# oLoRa-part-thi.net
KiCad netlist of a schematic drawn in EasyEDA
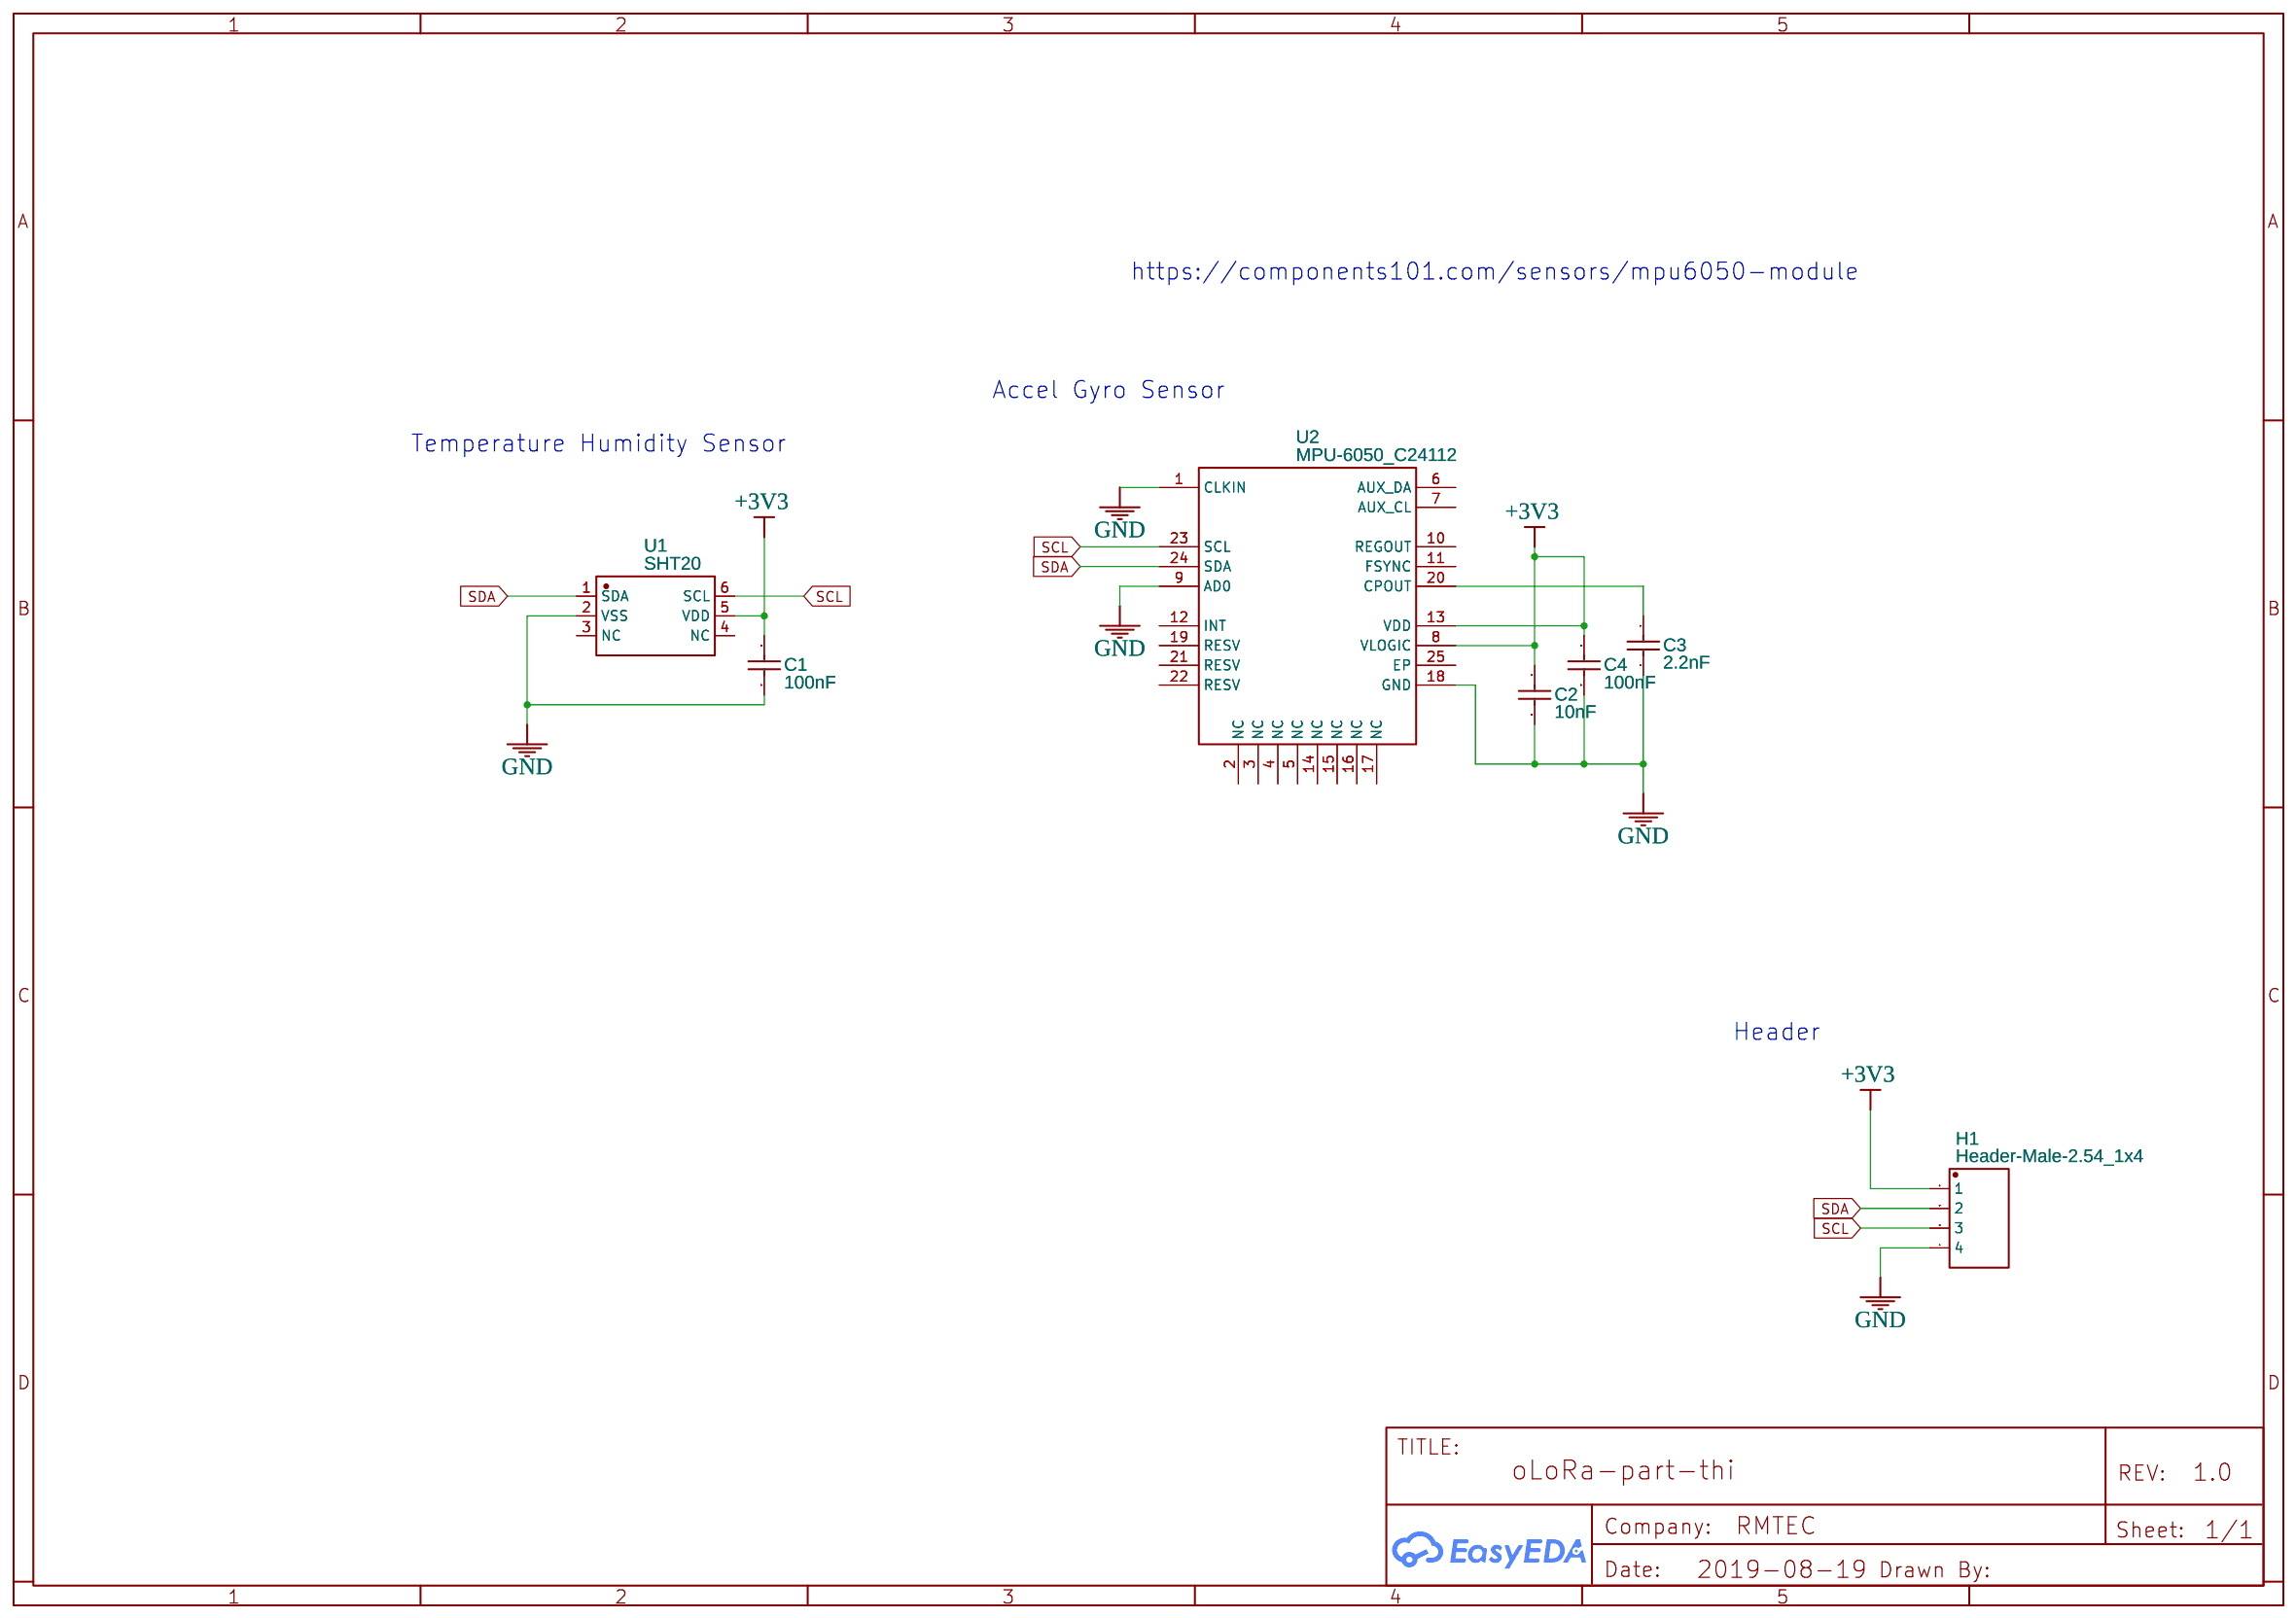
[diagram p0: schematic sheet]

(export (version "E")
  (design (tool "Eeschema 10.0.6"))
  (components
    (comp (ref "C1")
      (value "100nF")
      (fields
        (field (name "BOM_Manufacturer Part") "0603B104K500NT")
        (field (name "BOM_Supplier Part") "C30926")
      )
      (libsource (lib "") (part "0603B104K500NT"))
    )
    (comp (ref "C2")
      (value "10nF")
      (fields
        (field (name "BOM_Manufacturer Part") "CC0603KRX7R9BB103")
        (field (name "BOM_Supplier Part") "C100042")
      )
      (libsource (lib "") (part "CC0603KRX7R9BB103"))
    )
    (comp (ref "C3")
      (value "2.2nF")
      (fields
        (field (name "BOM_Manufacturer Part") "CC0603KRX7R9BB222")
        (field (name "BOM_Supplier Part") "C107082")
      )
      (libsource (lib "") (part "CC0603KRX7R9BB222"))
    )
    (comp (ref "C4")
      (value "100nF")
      (fields
        (field (name "BOM_Manufacturer Part") "0603B104K500NT")
        (field (name "BOM_Supplier Part") "C30926")
      )
      (libsource (lib "") (part "0603B104K500NT"))
    )
    (comp (ref "H1")
      (value "Header-Male-2.54_1x4")
      (fields
        (field (name "BOM_Manufacturer Part") "210S-1*4P L=11.6MMGold-plated black")
        (field (name "BOM_Supplier Part") "C124378")
      )
      (libsource (lib "") (part "Unknown_990_610"))
    )
    (comp (ref "U1")
      (value "SHT20")
      (fields (field (name "BOM_Supplier Part") "C53865"))
      (libsource (lib "") (part "Unknown_325_305"))
    )
    (comp (ref "U2")
      (value "MPU-6050_C24112")
      (fields (field (name "BOM_Manufacturer Part") "MPU-6050") (field (name "BOM_Supplier Part") "C24112"))
      (libsource (lib "") (part "Unknown_660_310"))
    )
  )
  (nets
    (net (code "1") (name "+3V3") (class "Default")
      (node (ref "C1") (pin "1") (pinfunction "1_1") (pintype "input"))
      (node (ref "C2") (pin "2") (pinfunction "2_2") (pintype "input"))
      (node (ref "C4") (pin "1") (pinfunction "1_1") (pintype "input"))
      (node (ref "H1") (pin "1") (pinfunction "1_1") (pintype "unspecified"))
      (node (ref "U1") (pin "5") (pinfunction "VDD_5") (pintype "unspecified"))
      (node (ref "U2") (pin "13") (pinfunction "VDD_13") (pintype "passive"))
      (node (ref "U2") (pin "8") (pinfunction "VLOGIC_8") (pintype "passive"))
    )
    (net (code "2") (name "GND") (class "Default")
      (node (ref "C1") (pin "2") (pinfunction "2_2") (pintype "input"))
      (node (ref "C2") (pin "1") (pinfunction "1_1") (pintype "input"))
      (node (ref "C3") (pin "1") (pinfunction "1_1") (pintype "input"))
      (node (ref "C4") (pin "2") (pinfunction "2_2") (pintype "input"))
      (node (ref "H1") (pin "4") (pinfunction "4_4") (pintype "unspecified"))
      (node (ref "U1") (pin "2") (pinfunction "VSS_2") (pintype "unspecified"))
      (node (ref "U2") (pin "1") (pinfunction "CLKIN_1") (pintype "input"))
      (node (ref "U2") (pin "18") (pinfunction "GND_18") (pintype "passive"))
      (node (ref "U2") (pin "9") (pinfunction "AD0_9") (pintype "input"))
    )
    (net (code "3") (name "Net-(U2-CPOUT)") (class "Default")
      (node (ref "C3") (pin "2") (pinfunction "2_2") (pintype "input"))
      (node (ref "U2") (pin "20") (pinfunction "CPOUT_20") (pintype "output"))
    )
    (net (code "4") (name "SCL") (class "Default")
      (node (ref "H1") (pin "3") (pinfunction "3_3") (pintype "unspecified"))
      (node (ref "U1") (pin "6") (pinfunction "SCL_6") (pintype "unspecified"))
      (node (ref "U2") (pin "23") (pinfunction "SCL_23") (pintype "input"))
    )
    (net (code "5") (name "SDA") (class "Default")
      (node (ref "H1") (pin "2") (pinfunction "2_2") (pintype "unspecified"))
      (node (ref "U1") (pin "1") (pinfunction "SDA_1") (pintype "unspecified"))
      (node (ref "U2") (pin "24") (pinfunction "SDA_24") (pintype "unspecified"))
    )
    (net (code "6") (name "unconnected-(U1-NC-Pad3)") (class "Default")
      (node (ref "U1") (pin "3") (pinfunction "NC_3") (pintype "unspecified"))
    )
    (net (code "7") (name "unconnected-(U1-NC-Pad4)") (class "Default")
      (node (ref "U1") (pin "4") (pinfunction "NC_4") (pintype "unspecified"))
    )
    (net (code "8") (name "unconnected-(U2-AUX_CL-Pad7)") (class "Default")
      (node (ref "U2") (pin "7") (pinfunction "AUX_CL_7") (pintype "unspecified"))
    )
    (net (code "9") (name "unconnected-(U2-AUX_DA-Pad6)") (class "Default")
      (node (ref "U2") (pin "6") (pinfunction "AUX_DA_6") (pintype "unspecified"))
    )
    (net (code "10") (name "unconnected-(U2-EP-Pad25)") (class "Default")
      (node (ref "U2") (pin "25") (pinfunction "EP_25") (pintype "passive"))
    )
    (net (code "11") (name "unconnected-(U2-FSYNC-Pad11)") (class "Default")
      (node (ref "U2") (pin "11") (pinfunction "FSYNC_11") (pintype "input"))
    )
    (net (code "12") (name "unconnected-(U2-INT-Pad12)") (class "Default")
      (node (ref "U2") (pin "12") (pinfunction "INT_12") (pintype "unspecified"))
    )
    (net (code "13") (name "unconnected-(U2-NC-Pad2)") (class "Default")
      (node (ref "U2") (pin "2") (pinfunction "NC_2") (pintype "unspecified"))
    )
    (net (code "14") (name "unconnected-(U2-NC-Pad3)") (class "Default")
      (node (ref "U2") (pin "3") (pinfunction "NC_3") (pintype "unspecified"))
    )
    (net (code "15") (name "unconnected-(U2-NC-Pad4)") (class "Default")
      (node (ref "U2") (pin "4") (pinfunction "NC_4") (pintype "unspecified"))
    )
    (net (code "16") (name "unconnected-(U2-NC-Pad5)") (class "Default")
      (node (ref "U2") (pin "5") (pinfunction "NC_5") (pintype "unspecified"))
    )
    (net (code "17") (name "unconnected-(U2-NC-Pad14)") (class "Default")
      (node (ref "U2") (pin "14") (pinfunction "NC_14") (pintype "unspecified"))
    )
    (net (code "18") (name "unconnected-(U2-NC-Pad15)") (class "Default")
      (node (ref "U2") (pin "15") (pinfunction "NC_15") (pintype "unspecified"))
    )
    (net (code "19") (name "unconnected-(U2-NC-Pad16)") (class "Default")
      (node (ref "U2") (pin "16") (pinfunction "NC_16") (pintype "unspecified"))
    )
    (net (code "20") (name "unconnected-(U2-NC-Pad17)") (class "Default")
      (node (ref "U2") (pin "17") (pinfunction "NC_17") (pintype "unspecified"))
    )
    (net (code "21") (name "unconnected-(U2-REGOUT-Pad10)") (class "Default")
      (node (ref "U2") (pin "10") (pinfunction "REGOUT_10") (pintype "output"))
    )
    (net (code "22") (name "unconnected-(U2-RESV-Pad19)") (class "Default")
      (node (ref "U2") (pin "19") (pinfunction "RESV_19") (pintype "unspecified"))
    )
    (net (code "23") (name "unconnected-(U2-RESV-Pad21)") (class "Default")
      (node (ref "U2") (pin "21") (pinfunction "RESV_21") (pintype "unspecified"))
    )
    (net (code "24") (name "unconnected-(U2-RESV-Pad22)") (class "Default")
      (node (ref "U2") (pin "22") (pinfunction "RESV_22") (pintype "unspecified"))
    )
  )
)
